# 02_LED_7.net
KiCad netlist of a schematic drawn in Altium Designer
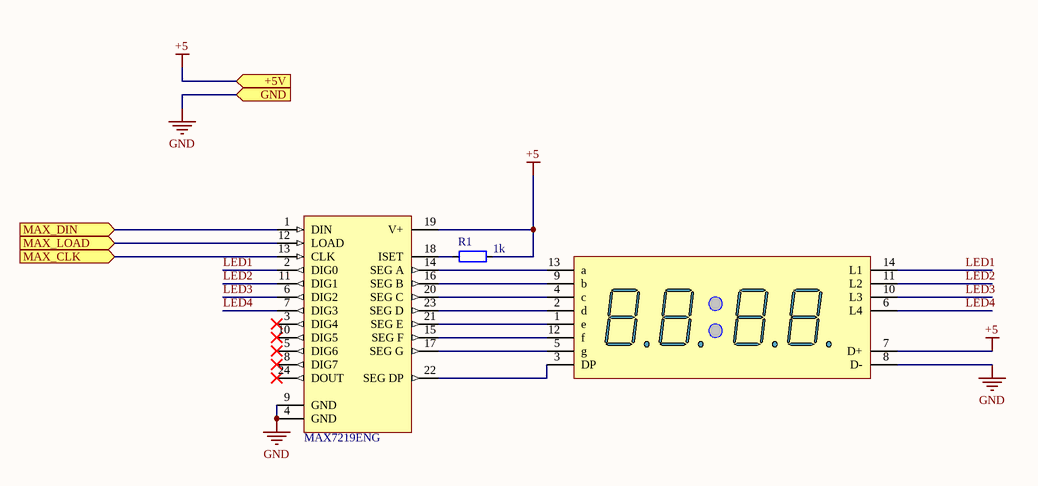
[diagram p0: [02] LED 7.SchDoc]

(export (version "E")
  (design (tool "Eeschema 10.0.6"))
  (components
    (comp (ref "L1")
      (value "Led 7 Seg 4 digit - Anode")
      (footprint "LED7SEG-4-0.56-RG")
      (libsource (lib "My Library") (part "LED7SEG-4-RG"))
    )
    (comp (ref "M1")
      (value "MAX7219ENG")
      (footprint "SO24")
      (description "Serially Interfaced, 8-Digit LED Display Driver")
      (fields (field (name "PUBLISHER") "Altium Limited"))
      (libsource (lib "My Library") (part "MAX7219ENG"))
    )
    (comp (ref "R1")
      (value "1k")
      (footprint "RES-1/2W")
      (description "Resistor - DIP")
      (libsource (lib "My Library") (part "Resistor - DIP"))
    )
  )
  (nets
    (net (code "1") (name "+5") (class "Default")
      (node (ref "L1") (pin "7") (pinfunction "D+_7") (pintype "passive"))
      (node (ref "M1") (pin "19") (pinfunction "V+_19") (pintype "power_in"))
      (node (ref "R1") (pin "1") (pinfunction "1_1") (pintype "passive"))
    )
    (net (code "2") (name "/LED1") (class "Default")
      (node (ref "L1") (pin "14") (pinfunction "L1_14") (pintype "passive"))
      (node (ref "M1") (pin "2") (pinfunction "DIG0_2") (pintype "output"))
    )
    (net (code "3") (name "/LED2") (class "Default")
      (node (ref "L1") (pin "11") (pinfunction "L2_11") (pintype "passive"))
      (node (ref "M1") (pin "11") (pinfunction "DIG1_11") (pintype "output"))
    )
    (net (code "4") (name "/LED3") (class "Default")
      (node (ref "L1") (pin "10") (pinfunction "L3_10") (pintype "passive"))
      (node (ref "M1") (pin "6") (pinfunction "DIG2_6") (pintype "output"))
    )
    (net (code "5") (name "/LED4") (class "Default")
      (node (ref "L1") (pin "6") (pinfunction "L4_6") (pintype "passive"))
      (node (ref "M1") (pin "7") (pinfunction "DIG3_7") (pintype "output"))
    )
    (net (code "6") (name "/MAX_CLK") (class "Default")
      (node (ref "M1") (pin "13") (pinfunction "CLK_13") (pintype "input"))
    )
    (net (code "7") (name "/MAX_DIN") (class "Default")
      (node (ref "M1") (pin "1") (pinfunction "DIN_1") (pintype "input"))
    )
    (net (code "8") (name "/MAX_LOAD") (class "Default")
      (node (ref "M1") (pin "12") (pinfunction "LOAD_12") (pintype "input"))
    )
    (net (code "9") (name "GND") (class "Default")
      (node (ref "L1") (pin "8") (pinfunction "D-_8") (pintype "passive"))
      (node (ref "M1") (pin "4") (pinfunction "GND_4") (pintype "power_in"))
      (node (ref "M1") (pin "9") (pinfunction "GND_9") (pintype "power_in"))
    )
    (net (code "10") (name "Net-(L1-DP)") (class "Default")
      (node (ref "L1") (pin "3") (pinfunction "DP_3") (pintype "passive"))
      (node (ref "M1") (pin "22") (pinfunction "SEG_DP_22") (pintype "output"))
    )
    (net (code "11") (name "Net-(L1-a)") (class "Default")
      (node (ref "L1") (pin "13") (pinfunction "a_13") (pintype "passive"))
      (node (ref "M1") (pin "14") (pinfunction "SEG_A_14") (pintype "output"))
    )
    (net (code "12") (name "Net-(L1-b)") (class "Default")
      (node (ref "L1") (pin "9") (pinfunction "b_9") (pintype "passive"))
      (node (ref "M1") (pin "16") (pinfunction "SEG_B_16") (pintype "output"))
    )
    (net (code "13") (name "Net-(L1-c)") (class "Default")
      (node (ref "L1") (pin "4") (pinfunction "c_4") (pintype "passive"))
      (node (ref "M1") (pin "20") (pinfunction "SEG_C_20") (pintype "output"))
    )
    (net (code "14") (name "Net-(L1-d)") (class "Default")
      (node (ref "L1") (pin "2") (pinfunction "d_2") (pintype "passive"))
      (node (ref "M1") (pin "23") (pinfunction "SEG_D_23") (pintype "output"))
    )
    (net (code "15") (name "Net-(L1-e)") (class "Default")
      (node (ref "L1") (pin "1") (pinfunction "e_1") (pintype "passive"))
      (node (ref "M1") (pin "21") (pinfunction "SEG_E_21") (pintype "output"))
    )
    (net (code "16") (name "Net-(L1-f)") (class "Default")
      (node (ref "L1") (pin "12") (pinfunction "f_12") (pintype "passive"))
      (node (ref "M1") (pin "15") (pinfunction "SEG_F_15") (pintype "output"))
    )
    (net (code "17") (name "Net-(L1-g)") (class "Default")
      (node (ref "L1") (pin "5") (pinfunction "g_5") (pintype "passive"))
      (node (ref "M1") (pin "17") (pinfunction "SEG_G_17") (pintype "output"))
    )
    (net (code "18") (name "Net-(M1-ISET)") (class "Default")
      (node (ref "M1") (pin "18") (pinfunction "ISET_18") (pintype "passive"))
      (node (ref "R1") (pin "2") (pinfunction "2_2") (pintype "passive"))
    )
    (net (code "19") (name "unconnected-(M1-DIG4-Pad3)") (class "Default")
      (node (ref "M1") (pin "3") (pinfunction "DIG4_3") (pintype "output+no_connect"))
    )
    (net (code "20") (name "unconnected-(M1-DIG5-Pad10)") (class "Default")
      (node (ref "M1") (pin "10") (pinfunction "DIG5_10") (pintype "output+no_connect"))
    )
    (net (code "21") (name "unconnected-(M1-DIG6-Pad5)") (class "Default")
      (node (ref "M1") (pin "5") (pinfunction "DIG6_5") (pintype "output+no_connect"))
    )
    (net (code "22") (name "unconnected-(M1-DIG7-Pad8)") (class "Default")
      (node (ref "M1") (pin "8") (pinfunction "DIG7_8") (pintype "output+no_connect"))
    )
    (net (code "23") (name "unconnected-(M1-DOUT-Pad24)") (class "Default")
      (node (ref "M1") (pin "24") (pinfunction "DOUT_24") (pintype "output+no_connect"))
    )
  )
)
